# TUSB320_Schematic.net
KiCad netlist of a schematic drawn in Altium Designer
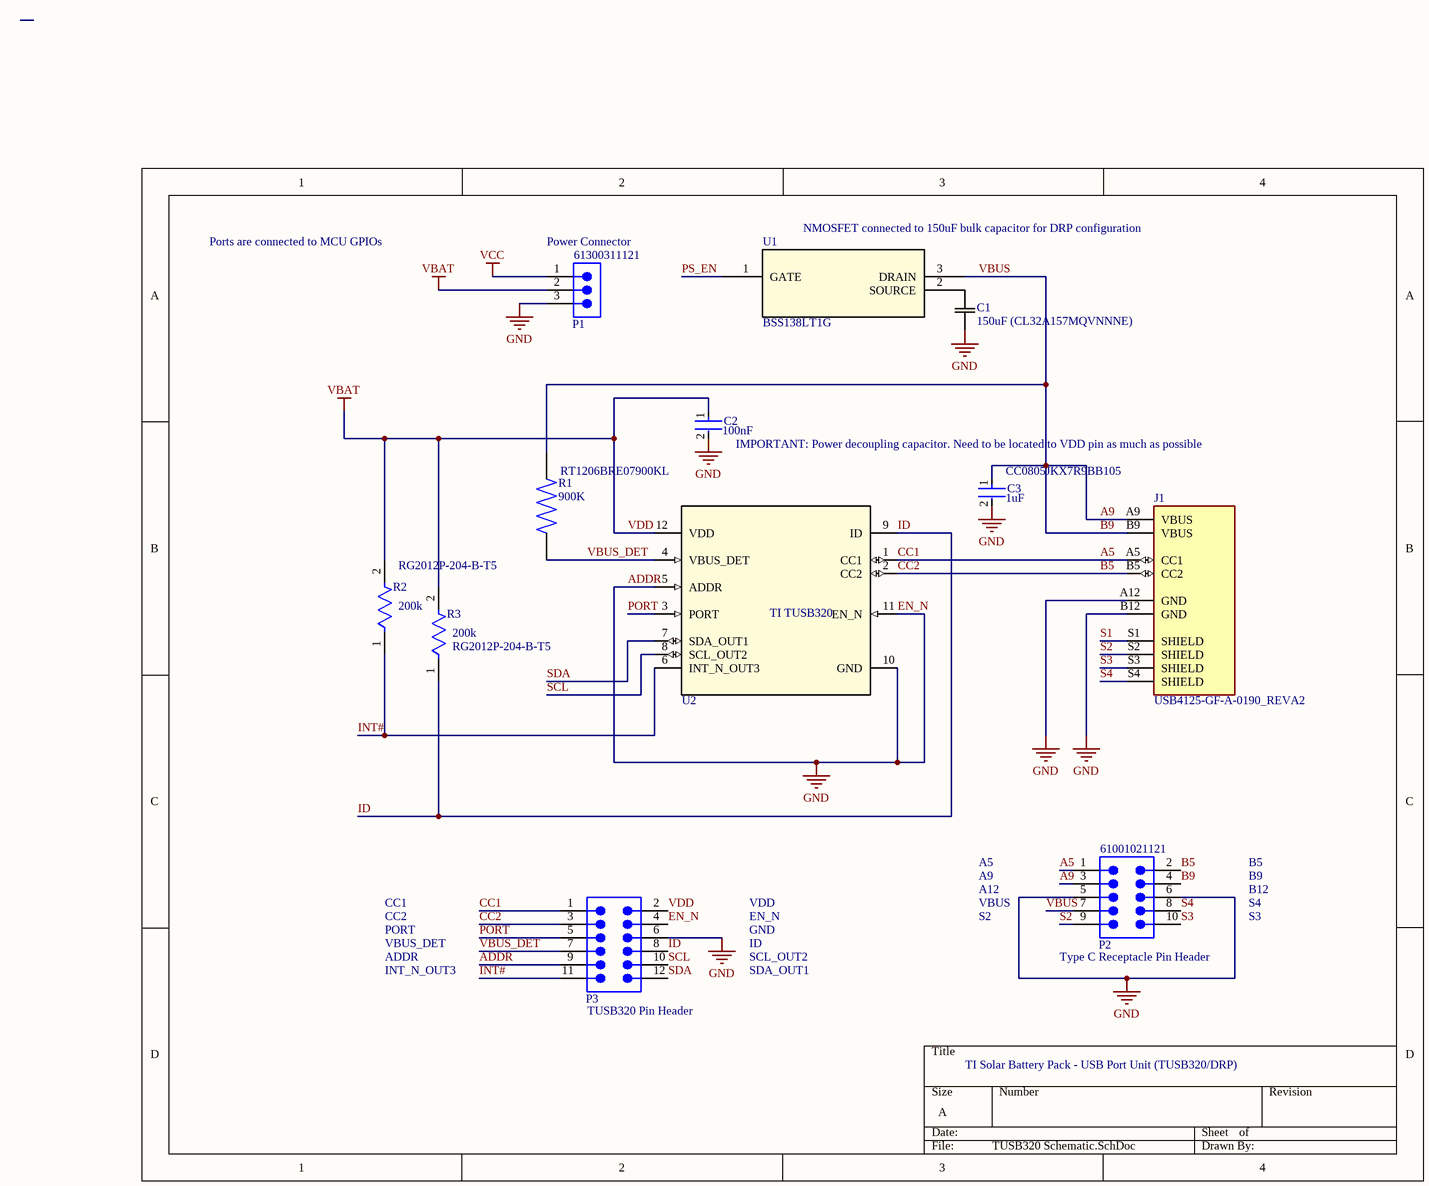
[diagram p0: TUSB320 Schematic.SchDoc]

(export (version "E")
  (design (tool "Eeschema 10.0.6"))
  (components
    (comp (ref "C1")
      (value "150uF (CL32A157MQVNNNE)")
      (footprint "CAP_CL32_SAM")
      (description "No Description Available")
      (libsource (lib "CL32A157MQVNNNE") (part "CL32A157MQVNNNE"))
    )
    (comp (ref "C2")
      (value "GRMJN65C1H104GE01J")
      (footprint "FP-GRMJN6-0_1-MFG")
      (description "GRMJN65C1H104GE01J Multilayer Ceramic Capacitor, 0.1 uF, 50 V, ± 2%, C0G (NP0), 0704 [1810 Metric]")
      (fields (field (name "TOLERANCE") "2%") (field (name "CAPACITANCE") "100nF"))
      (libsource (lib "Altium Content Vault") (part "02cd4be3c70576c341d710602a673aa"))
    )
    (comp (ref "C3")
      (value "CC0805JKX7R9BB105")
      (footprint "FP-CC0805-0_2-1_45-MFG")
      (description "CAP CER 1UF 50V X7R 0805")
      (fields (field (name "CAPACITANCE") "1uF") (field (name "TOLERANCE") "5%"))
      (libsource (lib "Altium Content Vault") (part "02cd4be3c70576c341d710602a673aa"))
    )
    (comp (ref "J1")
      (value "USB4125-GF-A-0190_REVA2")
      (footprint "GCT_USB4125-GF-A-0190_REVA2")
      (description "Type C Receptacle, Horizontal, SMT, For Power Charging Only")
      (fields (field (name "MF") "Global Connector Technology") (field (name "MP") "USB4125-GF-A-0190"))
      (libsource (lib "USB4125-GF-A-0190_REVA2") (part "USB4125-GF-A-0190_REVA2"))
    )
    (comp (ref "P1")
      (value "61300311121")
      (footprint "61300311121")
      (description "WR-PHD Pin Header, THT, Vertical, pitch 2.54mm, 1 Row, 3P")
      (fields (field (name "MANUFACTURER") "Wurth Elektronik"))
      (libsource (lib "Altium_WR-PHD_rev24a") (part "61300311121"))
    )
    (comp (ref "P2")
      (value "61001021121")
      (footprint "61001021121")
      (description "WR-PHD Pin Header, SMT, Vertical, pitch 2.54mm, 2 Row, 10P")
      (fields (field (name "MANUFACTURER") "Wurth Elektronik"))
      (libsource (lib "Altium_WR-PHD_rev24a") (part "61001021121"))
    )
    (comp (ref "P3")
      (value "61001221121")
      (footprint "61001221121")
      (description "WR-PHD Pin Header, SMT, Vertical, pitch 2.54mm, 2 Row, 12P")
      (fields (field (name "MANUFACTURER") "Wurth Elektronik"))
      (libsource (lib "Altium_WR-PHD_rev24a") (part "61001221121"))
    )
    (comp (ref "R1")
      (value "RT1206BRE07900KL")
      (footprint "RESC3116X65N")
      (fields (field (name "ALTIUM_VALUE") "900K"))
      (libsource (lib "RT1206BRE07900KL") (part "RT1206BRE07900KL"))
    )
    (comp (ref "R2")
      (value "RG2012P-204-B-T5")
      (footprint "FP-RG2012-IPC_B")
      (description "Automotive Metal Thin Film Chip Resistor, 0805, 200kΩ, 0.1%, 25ppm/°C, 0.125W, 150V")
      (fields (field (name "RESISTANCE") "200k") (field (name "TOLERANCE") "0.1%"))
      (libsource (lib "Altium Content Vault") (part "1029c3af85768c4190bb7ad29bc67b5"))
    )
    (comp (ref "R3")
      (value "RG2012P-204-B-T5")
      (footprint "FP-RG2012-IPC_B")
      (description "Automotive Metal Thin Film Chip Resistor, 0805, 200kΩ, 0.1%, 25ppm/°C, 0.125W, 150V")
      (fields (field (name "RESISTANCE") "200k") (field (name "TOLERANCE") "0.1%"))
      (libsource (lib "Altium Content Vault") (part "1029c3af85768c4190bb7ad29bc67b5"))
    )
    (comp (ref "U1")
      (value "BSS138LT1G")
      (footprint "SOT-23-3_1P4X3P040_ONS")
      (description "No Description Available")
      (libsource (lib "BSS138LT1G") (part "BSS138LT1G"))
    )
    (comp (ref "U2")
      (value "TI TUSB320")
      (footprint "RWB0012A")
      (description "No Description Available")
      (libsource (lib "TUSB320IRWBR") (part "TUSB320IRWBR"))
    )
  )
  (nets
    (net (code "1") (name "/A5") (class "Default")
      (node (ref "J1") (pin "A5") (pinfunction "CC1_A5") (pintype "bidirectional"))
      (node (ref "P2") (pin "1") (pinfunction "1_1") (pintype "passive"))
      (node (ref "P3") (pin "1") (pinfunction "1_1") (pintype "passive"))
      (node (ref "U2") (pin "1") (pinfunction "CC1_1") (pintype "bidirectional"))
    )
    (net (code "2") (name "/A9") (class "Default")
      (node (ref "C3") (pin "1") (pinfunction "1_1") (pintype "passive"))
      (node (ref "J1") (pin "A9") (pinfunction "VBUS_A9") (pintype "power_in"))
      (node (ref "J1") (pin "B9") (pinfunction "VBUS_B9") (pintype "power_in"))
      (node (ref "P2") (pin "3") (pinfunction "3_3") (pintype "passive"))
      (node (ref "P2") (pin "4") (pinfunction "4_4") (pintype "passive"))
      (node (ref "P2") (pin "7") (pinfunction "7_7") (pintype "passive"))
      (node (ref "R1") (pin "2") (pinfunction "2_2") (pintype "passive"))
      (node (ref "U1") (pin "3") (pinfunction "DRAIN_3") (pintype "passive"))
    )
    (net (code "3") (name "/B5") (class "Default")
      (node (ref "J1") (pin "B5") (pinfunction "CC2_B5") (pintype "bidirectional"))
      (node (ref "P2") (pin "2") (pinfunction "2_2") (pintype "passive"))
      (node (ref "P3") (pin "3") (pinfunction "3_3") (pintype "passive"))
      (node (ref "U2") (pin "2") (pinfunction "CC2_2") (pintype "bidirectional"))
    )
    (net (code "4") (name "/ID") (class "Default")
      (node (ref "P3") (pin "8") (pinfunction "8_8") (pintype "passive"))
      (node (ref "R3") (pin "1") (pinfunction "1_1") (pintype "passive"))
      (node (ref "U2") (pin "9") (pinfunction "ID_9") (pintype "open_collector"))
    )
    (net (code "5") (name "/INT#") (class "Default")
      (node (ref "P3") (pin "11") (pinfunction "11_11") (pintype "passive"))
      (node (ref "R2") (pin "1") (pinfunction "1_1") (pintype "passive"))
      (node (ref "U2") (pin "6") (pinfunction "INT_N_OUT3_6") (pintype "open_collector"))
    )
    (net (code "6") (name "/PORT") (class "Default")
      (node (ref "P3") (pin "5") (pinfunction "5_5") (pintype "passive"))
      (node (ref "U2") (pin "3") (pinfunction "PORT_3") (pintype "input"))
    )
    (net (code "7") (name "/PS_EN") (class "Default")
      (node (ref "U1") (pin "1") (pinfunction "GATE_1") (pintype "passive"))
    )
    (net (code "8") (name "/S1") (class "Default")
      (node (ref "J1") (pin "S1") (pinfunction "SHIELD_S1") (pintype "passive"))
    )
    (net (code "9") (name "/S2") (class "Default")
      (node (ref "J1") (pin "S2") (pinfunction "SHIELD_S2") (pintype "passive"))
      (node (ref "P2") (pin "9") (pinfunction "9_9") (pintype "passive"))
    )
    (net (code "10") (name "/S3") (class "Default")
      (node (ref "J1") (pin "S3") (pinfunction "SHIELD_S3") (pintype "passive"))
      (node (ref "P2") (pin "10") (pinfunction "10_10") (pintype "passive"))
    )
    (net (code "11") (name "/S4") (class "Default")
      (node (ref "J1") (pin "S4") (pinfunction "SHIELD_S4") (pintype "passive"))
      (node (ref "P2") (pin "8") (pinfunction "8_8") (pintype "passive"))
    )
    (net (code "12") (name "/SCL") (class "Default")
      (node (ref "P3") (pin "10") (pinfunction "10_10") (pintype "passive"))
      (node (ref "U2") (pin "8") (pinfunction "SCL_OUT2_8") (pintype "bidirectional"))
    )
    (net (code "13") (name "/SDA") (class "Default")
      (node (ref "P3") (pin "12") (pinfunction "12_12") (pintype "passive"))
      (node (ref "U2") (pin "7") (pinfunction "SDA_OUT1_7") (pintype "bidirectional"))
    )
    (net (code "14") (name "/VBUS_DET") (class "Default")
      (node (ref "P3") (pin "7") (pinfunction "7_7") (pintype "passive"))
      (node (ref "R1") (pin "1") (pinfunction "1_1") (pintype "passive"))
      (node (ref "U2") (pin "4") (pinfunction "VBUS_DET_4") (pintype "input"))
    )
    (net (code "15") (name "GND") (class "Default")
      (node (ref "C1") (pin "1") (pinfunction "1_1") (pintype "passive"))
      (node (ref "C2") (pin "2") (pinfunction "2_2") (pintype "passive"))
      (node (ref "C3") (pin "2") (pinfunction "2_2") (pintype "passive"))
      (node (ref "J1") (pin "A12") (pinfunction "GND_A12") (pintype "power_in"))
      (node (ref "J1") (pin "B12") (pinfunction "GND_B12") (pintype "power_in"))
      (node (ref "P1") (pin "3") (pinfunction "3_3") (pintype "passive"))
      (node (ref "P2") (pin "5") (pinfunction "5_5") (pintype "passive"))
      (node (ref "P2") (pin "6") (pinfunction "6_6") (pintype "passive"))
      (node (ref "P3") (pin "4") (pinfunction "4_4") (pintype "passive"))
      (node (ref "P3") (pin "6") (pinfunction "6_6") (pintype "passive"))
      (node (ref "P3") (pin "9") (pinfunction "9_9") (pintype "passive"))
      (node (ref "U2") (pin "10") (pinfunction "GND_10") (pintype "power_in"))
      (node (ref "U2") (pin "11") (pinfunction "EN_N_11") (pintype "input"))
      (node (ref "U2") (pin "5") (pinfunction "ADDR_5") (pintype "input"))
    )
    (net (code "16") (name "Net-(U1-SOURCE)") (class "Default")
      (node (ref "C1") (pin "2") (pinfunction "2_2") (pintype "passive"))
      (node (ref "U1") (pin "2") (pinfunction "SOURCE_2") (pintype "passive"))
    )
    (net (code "17") (name "VBAT") (class "Default")
      (node (ref "C2") (pin "1") (pinfunction "1_1") (pintype "passive"))
      (node (ref "P1") (pin "2") (pinfunction "2_2") (pintype "passive"))
      (node (ref "P3") (pin "2") (pinfunction "2_2") (pintype "passive"))
      (node (ref "R2") (pin "2") (pinfunction "2_2") (pintype "passive"))
      (node (ref "R3") (pin "2") (pinfunction "2_2") (pintype "passive"))
      (node (ref "U2") (pin "12") (pinfunction "VDD_12") (pintype "power_in"))
    )
    (net (code "18") (name "VCC") (class "Default")
      (node (ref "P1") (pin "1") (pinfunction "1_1") (pintype "passive"))
    )
  )
)
